# 12-5Convertor.net
KiCad netlist of a schematic drawn in EAGLE
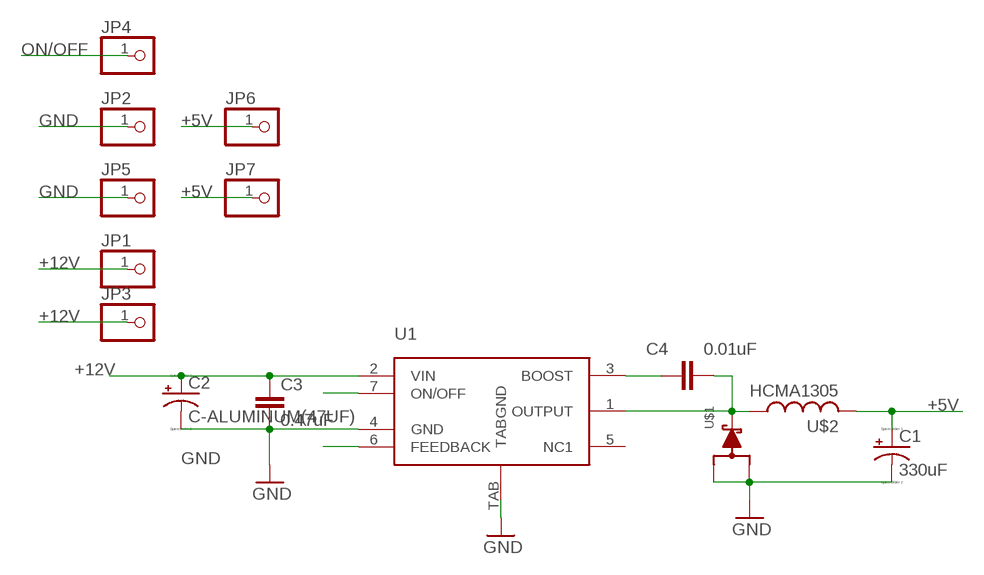
[diagram p0: schematic, sheet 1]

(export (version "E")
  (design (tool "Eeschema 10.0.6"))
  (components
    (comp (ref "C1")
      (value "330uF")
      (footprint "eagle-import:CPOL-US(10.3_10.3MM)")
      (libsource (lib "eagle-import") (part "C-ALUMINUM(330UF)"))
    )
    (comp (ref "C2")
      (value "C-ALUMINUM(47UF)")
      (footprint "eagle-import:CPOL-US(8.3_8.3MM)")
      (libsource (lib "eagle-import") (part "C-ALUMINUM(47UF)"))
    )
    (comp (ref "C3")
      (value "0.47uF")
      (footprint "eagle-import:0805")
      (libsource (lib "eagle-import") (part "CAP0805"))
    )
    (comp (ref "C4")
      (value "0.01uF")
      (footprint "eagle-import:0603-CAP")
      (libsource (lib "eagle-import") (part "SparkFun-Passives_CAP0603-CAP"))
    )
    (comp (ref "JP1")
      (value "PINHD-1X1")
      (footprint "eagle-import:1X01")
      (libsource (lib "eagle-import") (part "PINHD-1X1"))
    )
    (comp (ref "JP2")
      (value "PINHD-1X1")
      (footprint "eagle-import:1X01")
      (libsource (lib "eagle-import") (part "PINHD-1X1"))
    )
    (comp (ref "JP3")
      (value "PINHD-1X1")
      (footprint "eagle-import:1X01")
      (libsource (lib "eagle-import") (part "PINHD-1X1"))
    )
    (comp (ref "JP4")
      (value "PINHD-1X1")
      (footprint "eagle-import:1X01")
      (libsource (lib "eagle-import") (part "PINHD-1X1"))
    )
    (comp (ref "JP5")
      (value "PINHD-1X1")
      (footprint "eagle-import:1X01")
      (libsource (lib "eagle-import") (part "PINHD-1X1"))
    )
    (comp (ref "JP6")
      (value "PINHD-1X1")
      (footprint "eagle-import:1X01")
      (libsource (lib "eagle-import") (part "PINHD-1X1"))
    )
    (comp (ref "JP7")
      (value "PINHD-1X1")
      (footprint "eagle-import:1X01")
      (libsource (lib "eagle-import") (part "PINHD-1X1"))
    )
    (comp (ref "U$1")
      (value "SWITCHMODE_SCHOTTKY")
      (footprint "eagle-import:DPAK-3")
      (libsource (lib "eagle-import") (part "SWITCHMODE_SCHOTTKY"))
    )
    (comp (ref "U$2")
      (value "HCMA1305")
      (footprint "eagle-import:HCMA1305")
      (libsource (lib "eagle-import") (part "HCMA1305"))
    )
    (comp (ref "U1")
      (value "LM2678")
      (footprint "eagle-import:LM2678")
      (libsource (lib "eagle-import") (part "LM2678"))
    )
  )
  (nets
    (net (code "1") (name "/+5V") (class "Default")
      (node (ref "C1") (pin "+") (pinfunction "+_+") (pintype "passive"))
      (node (ref "JP6") (pin "1") (pinfunction "1_1") (pintype "passive"))
      (node (ref "JP7") (pin "1") (pinfunction "1_1") (pintype "passive"))
      (node (ref "U$2") (pin "P$2") (pinfunction "2_P$2") (pintype "passive"))
      (node (ref "U1") (pin "6") (pinfunction "FEEDBACK_6") (pintype "bidirectional"))
    )
    (net (code "2") (name "/+12V") (class "Default")
      (node (ref "C2") (pin "+") (pinfunction "+_+") (pintype "passive"))
      (node (ref "C3") (pin "1") (pinfunction "1_1") (pintype "passive"))
      (node (ref "JP1") (pin "1") (pinfunction "1_1") (pintype "passive"))
      (node (ref "JP3") (pin "1") (pinfunction "1_1") (pintype "passive"))
      (node (ref "U1") (pin "2") (pinfunction "VIN_2") (pintype "bidirectional"))
    )
    (net (code "3") (name "/ON{slash}OFF") (class "Default")
      (node (ref "JP4") (pin "1") (pinfunction "1_1") (pintype "passive"))
      (node (ref "U1") (pin "7") (pinfunction "ON/OFF_7") (pintype "bidirectional"))
    )
    (net (code "4") (name "GND") (class "Default")
      (node (ref "C1") (pin "-") (pinfunction "-_-") (pintype "passive"))
      (node (ref "C2") (pin "-") (pinfunction "-_-") (pintype "passive"))
      (node (ref "C3") (pin "2") (pinfunction "2_2") (pintype "passive"))
      (node (ref "JP2") (pin "1") (pinfunction "1_1") (pintype "passive"))
      (node (ref "JP5") (pin "1") (pinfunction "1_1") (pintype "passive"))
      (node (ref "U$1") (pin "P$1") (pinfunction "P$1_P$1") (pintype "bidirectional"))
      (node (ref "U$1") (pin "P$3") (pinfunction "P$3_P$3") (pintype "bidirectional"))
      (node (ref "U1") (pin "4") (pinfunction "GND_4") (pintype "bidirectional"))
      (node (ref "U1") (pin "TAB") (pinfunction "TABGND_TAB") (pintype "bidirectional"))
    )
    (net (code "5") (name "Net-(U$2-1)") (class "Default")
      (node (ref "C4") (pin "2") (pinfunction "2_2") (pintype "passive"))
      (node (ref "U$1") (pin "P$4") (pinfunction "P$4_P$4") (pintype "bidirectional"))
      (node (ref "U$2") (pin "P$1") (pinfunction "1_P$1") (pintype "passive"))
      (node (ref "U1") (pin "1") (pinfunction "OUTPUT_1") (pintype "bidirectional"))
    )
    (net (code "6") (name "Net-(U1-BOOST)") (class "Default")
      (node (ref "C4") (pin "1") (pinfunction "1_1") (pintype "passive"))
      (node (ref "U1") (pin "3") (pinfunction "BOOST_3") (pintype "bidirectional"))
    )
    (net (code "7") (name "unconnected-(U1-NC1-Pad5)") (class "Default")
      (node (ref "U1") (pin "5") (pinfunction "NC1_5") (pintype "no_connect"))
    )
  )
)
